# battery.net
KiCad netlist of a schematic drawn in EasyEDA Pro
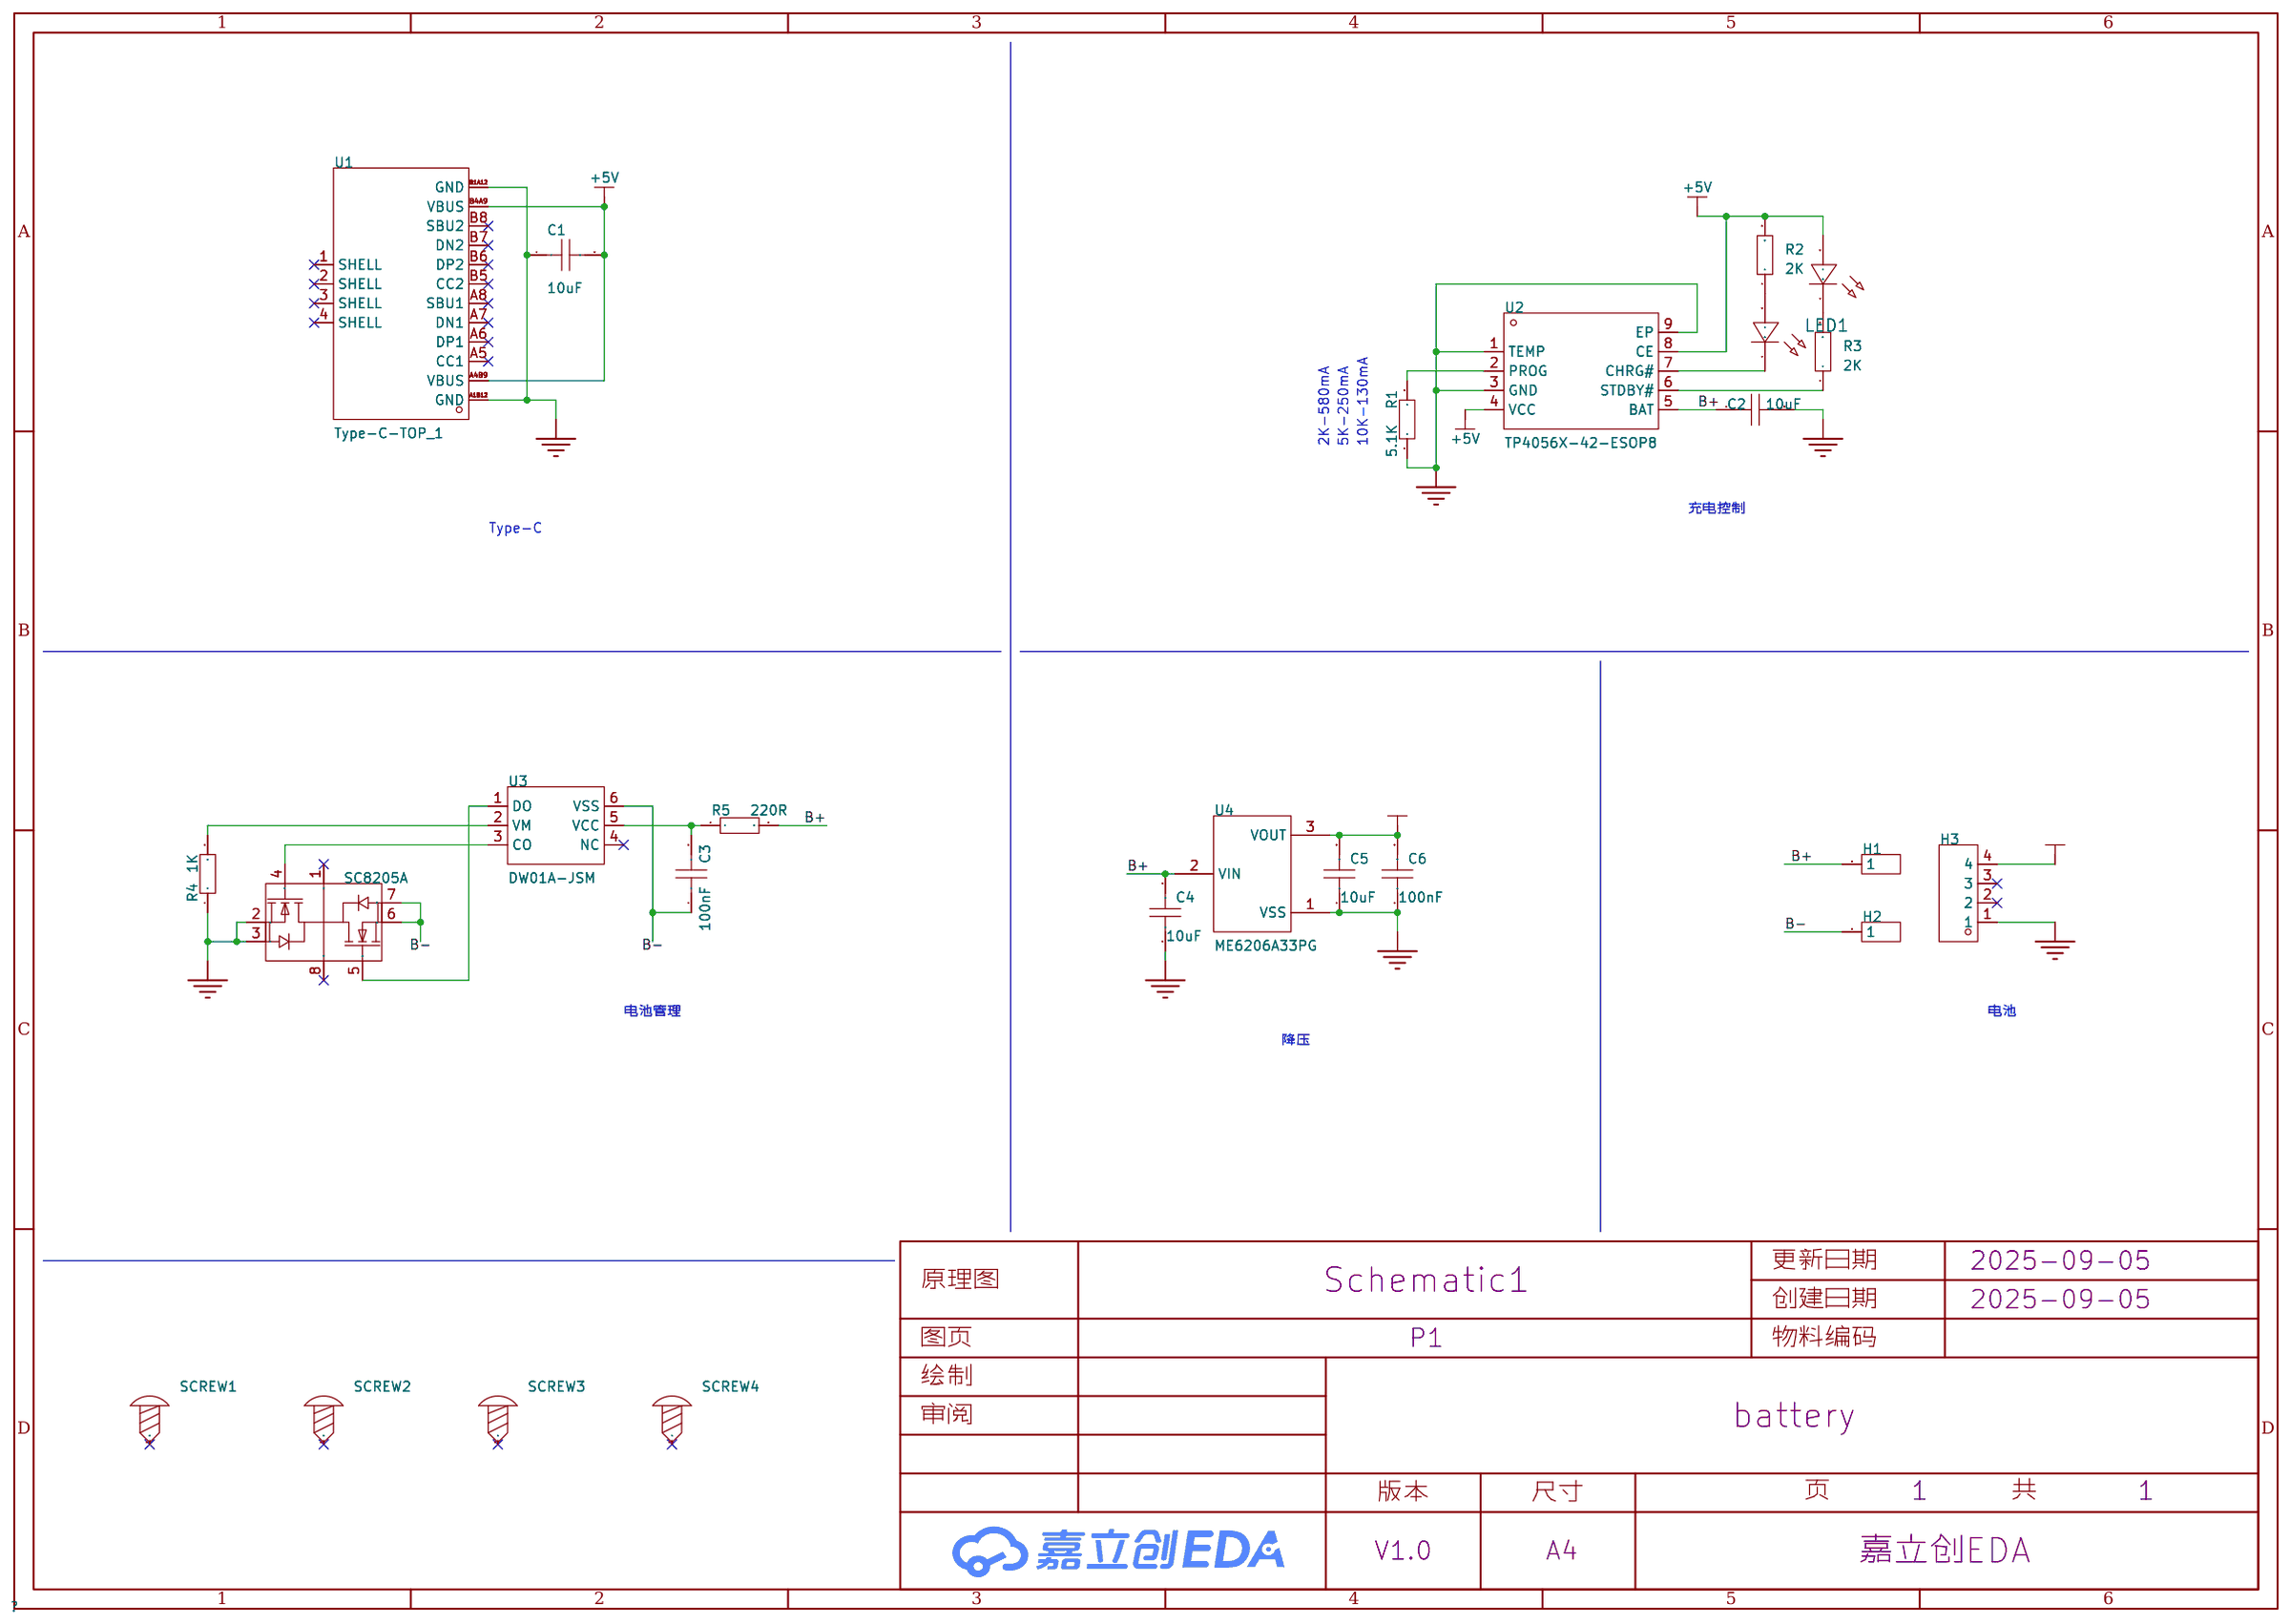
[diagram p0: schematic sheet]

(export (version "E")
  (design (tool "Eeschema 10.0.6"))
  (components
    (comp (ref "C1")
      (value "10uF")
      (footprint "easyedapro:C0805")
      (libsource (lib "easyedapro") (part "CapAcitance"))
    )
    (comp (ref "C2")
      (value "10uF")
      (footprint "easyedapro:C0805")
      (libsource (lib "easyedapro") (part "CapAcitance"))
    )
    (comp (ref "C3")
      (value "100nF")
      (footprint "easyedapro:C0805")
      (libsource (lib "easyedapro") (part "CapAcitance"))
    )
    (comp (ref "C4")
      (value "10uF")
      (footprint "easyedapro:C0805")
      (libsource (lib "easyedapro") (part "CapAcitance"))
    )
    (comp (ref "C5")
      (value "10uF")
      (footprint "easyedapro:C0805")
      (libsource (lib "easyedapro") (part "CapAcitance"))
    )
    (comp (ref "C6")
      (value "100nF")
      (footprint "easyedapro:C0805")
      (libsource (lib "easyedapro") (part "CapAcitance"))
    )
    (comp (ref "H1")
      (value "~")
      (footprint "easyedapro:HDR-TH_1P-V-M_XKB_X4611WV-01I-C28D40")
      (libsource (lib "easyedapro") (part "HDR_1x1"))
    )
    (comp (ref "H2")
      (value "~")
      (footprint "easyedapro:HDR-TH_1P-V-M_XKB_X4611WV-01I-C28D40")
      (libsource (lib "easyedapro") (part "HDR_1x1"))
    )
    (comp (ref "H3")
      (value "~")
      (footprint "easyedapro:HDR-TH_4P-P2.54-V-M")
      (libsource (lib "easyedapro") (part "PZ254V-11-04P"))
    )
    (comp (ref "LED1")
      (value "~")
      (footprint "easyedapro:LED_0805")
      (libsource (lib "easyedapro") (part "LED_R"))
    )
    (comp (ref "LED2")
      (value "~")
      (footprint "easyedapro:LED_0805")
      (libsource (lib "easyedapro") (part "LED_G"))
    )
    (comp (ref "Q1")
      (value "SC8205A")
      (footprint "easyedapro:TSSOP-8_L4.4-W3.0-P0.65-LS6.4-BL")
      (description "数量:2个N沟道;漏源电压(Vdss):20V;连续漏极电流(Id):-;导通电阻(RDS(on)):25mΩ@10V,5A;耗散功率(Pd):2W;阈值电压(Vgs(th)):1.5V;")
      (fields (field (name "Manufacturer") "FM(富满)"))
      (libsource (lib "easyedapro") (part "SC8205A"))
    )
    (comp (ref "R1") (value "5.1K") (footprint "easyedapro:R0805") (libsource (lib "easyedapro") (part "电阻")))
    (comp (ref "R2") (value "2K") (footprint "easyedapro:R0805") (libsource (lib "easyedapro") (part "电阻")))
    (comp (ref "R3") (value "2K") (footprint "easyedapro:R0805") (libsource (lib "easyedapro") (part "电阻")))
    (comp (ref "R4") (value "1K") (footprint "easyedapro:R0805") (libsource (lib "easyedapro") (part "电阻")))
    (comp (ref "R5") (value "220R") (footprint "easyedapro:R0805") (libsource (lib "easyedapro") (part "电阻")))
    (comp (ref "SCREW1")
      (value "~")
      (footprint "easyedapro:M3螺丝")
      (libsource (lib "easyedapro") (part "螺丝孔"))
    )
    (comp (ref "SCREW2")
      (value "~")
      (footprint "easyedapro:M3螺丝")
      (libsource (lib "easyedapro") (part "螺丝孔"))
    )
    (comp (ref "SCREW3")
      (value "~")
      (footprint "easyedapro:M3螺丝")
      (libsource (lib "easyedapro") (part "螺丝孔"))
    )
    (comp (ref "SCREW4")
      (value "~")
      (footprint "easyedapro:M3螺丝")
      (libsource (lib "easyedapro") (part "螺丝孔"))
    )
    (comp (ref "U1")
      (value "Type-C-TOP_1")
      (footprint "easyedapro:USB-C-SMD_TYPE-C16PIN")
      (libsource (lib "easyedapro") (part "TYPE-C-TOP_1"))
    )
    (comp (ref "U2")
      (value "TP4056X-42-ESOP8")
      (footprint "easyedapro:SOP-8_L4.9-W3.9-P1.27-LS6.0-TL-EP")
      (description "工作电压:4V~8V;最大充电电流:1A;电池类型:锂离子/聚合物;电池节数:1;")
      (fields (field (name "Manufacturer") "TOPPOWER(南京拓微)"))
      (libsource (lib "easyedapro") (part "TP4056X_C2763448"))
    )
    (comp (ref "U3")
      (value "DW01A-JSM")
      (footprint "easyedapro:SOT-23-6_L2.9-W1.6-P0.95-LS2.8-BR")
      (description "工作电压:300mV~6V;最大充电电流:-;")
      (fields (field (name "Manufacturer") "JSMSEMI(杰盛微)"))
      (libsource (lib "easyedapro") (part "DW01A-JSM"))
    )
    (comp (ref "U4")
      (value "ME6206A33PG")
      (footprint "easyedapro:SOT-89-3_L4.5-W2.5-P1.50-LS4.2-BR")
      (description "输出类型:固定;工作电压:6V;输出电压:3.3V;输出电流:300mA;电源纹波抑制比(PSRR):50dB@(1kHz);输出极性:正极;")
      (fields (field (name "Manufacturer") "MICRONE(南京微盟)"))
      (libsource (lib "easyedapro") (part "ME6206A33PG"))
    )
  )
  (nets
    (net (code "1") (name "+3.3V") (class "Default")
      (node (ref "C5") (pin "2") (pinfunction "2_2") (pintype "input"))
      (node (ref "C6") (pin "2") (pinfunction "2_2") (pintype "input"))
      (node (ref "H3") (pin "4") (pinfunction "4_4") (pintype "unspecified"))
      (node (ref "U4") (pin "3") (pinfunction "VOUT_3") (pintype "unspecified"))
    )
    (net (code "2") (name "+5V") (class "Default")
      (node (ref "C1") (pin "2") (pinfunction "2_2") (pintype "input"))
      (node (ref "LED2") (pin "2") (pinfunction "A_2") (pintype "input"))
      (node (ref "R2") (pin "2") (pinfunction "2_2") (pintype "input"))
      (node (ref "U1") (pin "A4B9") (pinfunction "VBUS_A4B9") (pintype "unspecified"))
      (node (ref "U1") (pin "B4A9") (pinfunction "VBUS_B4A9") (pintype "unspecified"))
      (node (ref "U2") (pin "4") (pinfunction "VCC_4") (pintype "unspecified"))
      (node (ref "U2") (pin "8") (pinfunction "CE_8") (pintype "unspecified"))
    )
    (net (code "3") (name "/B+") (class "Default")
      (node (ref "C2") (pin "1") (pinfunction "1_1") (pintype "input"))
      (node (ref "C4") (pin "2") (pinfunction "2_2") (pintype "input"))
      (node (ref "H1") (pin "1") (pinfunction "1_1") (pintype "unspecified"))
      (node (ref "R5") (pin "2") (pinfunction "2_2") (pintype "input"))
      (node (ref "U2") (pin "5") (pinfunction "BAT_5") (pintype "unspecified"))
      (node (ref "U4") (pin "2") (pinfunction "VIN_2") (pintype "unspecified"))
    )
    (net (code "4") (name "/B-") (class "Default")
      (node (ref "C3") (pin "1") (pinfunction "1_1") (pintype "input"))
      (node (ref "H2") (pin "1") (pinfunction "1_1") (pintype "unspecified"))
      (node (ref "Q1") (pin "6") (pinfunction "S2_6") (pintype "unspecified"))
      (node (ref "Q1") (pin "7") (pinfunction "S2_7") (pintype "unspecified"))
      (node (ref "U3") (pin "6") (pinfunction "VSS_6") (pintype "unspecified"))
    )
    (net (code "5") (name "GND") (class "Default")
      (node (ref "C1") (pin "1") (pinfunction "1_1") (pintype "input"))
      (node (ref "C2") (pin "2") (pinfunction "2_2") (pintype "input"))
      (node (ref "C4") (pin "1") (pinfunction "1_1") (pintype "input"))
      (node (ref "C5") (pin "1") (pinfunction "1_1") (pintype "input"))
      (node (ref "C6") (pin "1") (pinfunction "1_1") (pintype "input"))
      (node (ref "H3") (pin "1") (pinfunction "1_1") (pintype "unspecified"))
      (node (ref "Q1") (pin "2") (pinfunction "S1_2") (pintype "unspecified"))
      (node (ref "Q1") (pin "3") (pinfunction "S1_3") (pintype "unspecified"))
      (node (ref "R1") (pin "1") (pinfunction "1_1") (pintype "input"))
      (node (ref "R4") (pin "1") (pinfunction "1_1") (pintype "input"))
      (node (ref "U1") (pin "A1B12") (pinfunction "GND_A1B12") (pintype "unspecified"))
      (node (ref "U1") (pin "B1A12") (pinfunction "GND_B1A12") (pintype "unspecified"))
      (node (ref "U2") (pin "1") (pinfunction "TEMP_1") (pintype "unspecified"))
      (node (ref "U2") (pin "3") (pinfunction "GND_3") (pintype "unspecified"))
      (node (ref "U2") (pin "9") (pinfunction "EP_9") (pintype "unspecified"))
      (node (ref "U4") (pin "1") (pinfunction "VSS_1") (pintype "unspecified"))
    )
    (net (code "6") (name "Net-(LED1-A)") (class "Default")
      (node (ref "LED1") (pin "2") (pinfunction "A_2") (pintype "input"))
      (node (ref "R2") (pin "1") (pinfunction "1_1") (pintype "input"))
    )
    (net (code "7") (name "Net-(LED1-C)") (class "Default")
      (node (ref "LED1") (pin "1") (pinfunction "C_1") (pintype "input"))
      (node (ref "U2") (pin "7") (pinfunction "CHRG#_7") (pintype "unspecified"))
    )
    (net (code "8") (name "Net-(LED2-C)") (class "Default")
      (node (ref "LED2") (pin "1") (pinfunction "C_1") (pintype "input"))
      (node (ref "R3") (pin "2") (pinfunction "2_2") (pintype "input"))
    )
    (net (code "9") (name "Net-(Q1-G1)") (class "Default")
      (node (ref "Q1") (pin "4") (pinfunction "G1_4") (pintype "unspecified"))
      (node (ref "U3") (pin "3") (pinfunction "CO_3") (pintype "unspecified"))
    )
    (net (code "10") (name "Net-(Q1-G2)") (class "Default")
      (node (ref "Q1") (pin "5") (pinfunction "G2_5") (pintype "unspecified"))
      (node (ref "U3") (pin "1") (pinfunction "DO_1") (pintype "unspecified"))
    )
    (net (code "11") (name "Net-(U2-PROG)") (class "Default")
      (node (ref "R1") (pin "2") (pinfunction "2_2") (pintype "input"))
      (node (ref "U2") (pin "2") (pinfunction "PROG_2") (pintype "unspecified"))
    )
    (net (code "12") (name "Net-(U2-STDBY#)") (class "Default")
      (node (ref "R3") (pin "1") (pinfunction "1_1") (pintype "input"))
      (node (ref "U2") (pin "6") (pinfunction "STDBY#_6") (pintype "unspecified"))
    )
    (net (code "13") (name "Net-(U3-VCC)") (class "Default")
      (node (ref "C3") (pin "2") (pinfunction "2_2") (pintype "input"))
      (node (ref "R5") (pin "1") (pinfunction "1_1") (pintype "input"))
      (node (ref "U3") (pin "5") (pinfunction "VCC_5") (pintype "unspecified"))
    )
    (net (code "14") (name "Net-(U3-VM)") (class "Default")
      (node (ref "R4") (pin "2") (pinfunction "2_2") (pintype "input"))
      (node (ref "U3") (pin "2") (pinfunction "VM_2") (pintype "unspecified"))
    )
    (net (code "15") (name "unconnected-(H3-Pad2)") (class "Default")
      (node (ref "H3") (pin "2") (pinfunction "2_2") (pintype "unspecified+no_connect"))
    )
    (net (code "16") (name "unconnected-(H3-Pad3)") (class "Default")
      (node (ref "H3") (pin "3") (pinfunction "3_3") (pintype "unspecified+no_connect"))
    )
    (net (code "17") (name "unconnected-(Q1-D12-Pad1)") (class "Default")
      (node (ref "Q1") (pin "1") (pinfunction "D12_1") (pintype "unspecified+no_connect"))
    )
    (net (code "18") (name "unconnected-(Q1-D12-Pad8)") (class "Default")
      (node (ref "Q1") (pin "8") (pinfunction "D12_8") (pintype "unspecified+no_connect"))
    )
    (net (code "19") (name "unconnected-(SCREW1-Pad1)") (class "Default")
      (node (ref "SCREW1") (pin "1") (pinfunction "1_1") (pintype "input+no_connect"))
    )
    (net (code "20") (name "unconnected-(SCREW2-Pad1)") (class "Default")
      (node (ref "SCREW2") (pin "1") (pinfunction "1_1") (pintype "input+no_connect"))
    )
    (net (code "21") (name "unconnected-(SCREW3-Pad1)") (class "Default")
      (node (ref "SCREW3") (pin "1") (pinfunction "1_1") (pintype "input+no_connect"))
    )
    (net (code "22") (name "unconnected-(SCREW4-Pad1)") (class "Default")
      (node (ref "SCREW4") (pin "1") (pinfunction "1_1") (pintype "input+no_connect"))
    )
    (net (code "23") (name "unconnected-(U1-CC1-PadA5)") (class "Default")
      (node (ref "U1") (pin "A5") (pinfunction "CC1_A5") (pintype "unspecified+no_connect"))
    )
    (net (code "24") (name "unconnected-(U1-CC2-PadB5)") (class "Default")
      (node (ref "U1") (pin "B5") (pinfunction "CC2_B5") (pintype "unspecified+no_connect"))
    )
    (net (code "25") (name "unconnected-(U1-DN1-PadA7)") (class "Default")
      (node (ref "U1") (pin "A7") (pinfunction "DN1_A7") (pintype "unspecified+no_connect"))
    )
    (net (code "26") (name "unconnected-(U1-DN2-PadB7)") (class "Default")
      (node (ref "U1") (pin "B7") (pinfunction "DN2_B7") (pintype "unspecified+no_connect"))
    )
    (net (code "27") (name "unconnected-(U1-DP1-PadA6)") (class "Default")
      (node (ref "U1") (pin "A6") (pinfunction "DP1_A6") (pintype "unspecified+no_connect"))
    )
    (net (code "28") (name "unconnected-(U1-DP2-PadB6)") (class "Default")
      (node (ref "U1") (pin "B6") (pinfunction "DP2_B6") (pintype "unspecified+no_connect"))
    )
    (net (code "29") (name "unconnected-(U1-SBU1-PadA8)") (class "Default")
      (node (ref "U1") (pin "A8") (pinfunction "SBU1_A8") (pintype "unspecified+no_connect"))
    )
    (net (code "30") (name "unconnected-(U1-SBU2-PadB8)") (class "Default")
      (node (ref "U1") (pin "B8") (pinfunction "SBU2_B8") (pintype "unspecified+no_connect"))
    )
    (net (code "31") (name "unconnected-(U1-SHELL-Pad1)") (class "Default")
      (node (ref "U1") (pin "1") (pinfunction "SHELL_1") (pintype "unspecified+no_connect"))
    )
    (net (code "32") (name "unconnected-(U1-SHELL-Pad2)") (class "Default")
      (node (ref "U1") (pin "2") (pinfunction "SHELL_2") (pintype "unspecified+no_connect"))
    )
    (net (code "33") (name "unconnected-(U1-SHELL-Pad3)") (class "Default")
      (node (ref "U1") (pin "3") (pinfunction "SHELL_3") (pintype "unspecified+no_connect"))
    )
    (net (code "34") (name "unconnected-(U1-SHELL-Pad4)") (class "Default")
      (node (ref "U1") (pin "4") (pinfunction "SHELL_4") (pintype "unspecified+no_connect"))
    )
    (net (code "35") (name "unconnected-(U3-NC-Pad4)") (class "Default")
      (node (ref "U3") (pin "4") (pinfunction "NC_4") (pintype "unspecified+no_connect"))
    )
  )
)
